# Sounder_Buzzer.net
KiCad netlist of a schematic drawn in Altium Designer
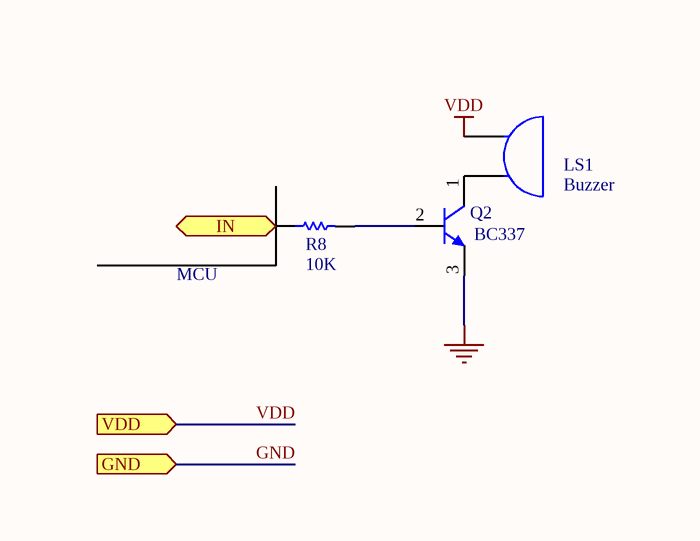
[diagram p0: Sounder_Buzzer.SchDoc]

(export (version "E")
  (design (tool "Eeschema 10.0.6"))
  (components
    (comp (ref "LS1")
      (value "Buzzer")
      (footprint "BUZZER")
      (fields (field (name "MANUFACTURER") "Generic Components") (field (name "PUBLISHER") "Altium Limited"))
      (libsource (lib "Miscellaneous Devices") (part "Buzzer"))
    )
    (comp (ref "Q2")
      (value "BC337")
      (footprint "TO92C")
      (description "NPN Bipolar Transistor")
      (fields
        (field (name "MANUFACTURER") "Generic Components")
        (field (name "Comment") "NPN")
        (field (name "PUBLISHER") "Altium Limited")
      )
      (libsource (lib "Miscellaneous Devices") (part "NPN"))
    )
    (comp (ref "R8")
      (value "10K")
      (footprint "AXIAL-0.4")
      (description "Resistor")
      (fields
        (field (name "MANUFACTURER") "Generic Components")
        (field (name "Comment") "Res1")
        (field (name "PUBLISHER") "Altium Limited")
      )
      (libsource (lib "Miscellaneous Devices") (part "Res1"))
    )
  )
  (nets
    (net (code "1") (name "/IN") (class "Default")
      (node (ref "R8") (pin "1") (pinfunction "1_1") (pintype "passive"))
    )
    (net (code "2") (name "GND") (class "Default")
      (node (ref "Q2") (pin "3") (pinfunction "E_3") (pintype "passive"))
    )
    (net (code "3") (name "Net-(LS1-B)") (class "Default")
      (node (ref "LS1") (pin "2") (pinfunction "B_2") (pintype "passive"))
      (node (ref "Q2") (pin "1") (pinfunction "C_1") (pintype "passive"))
    )
    (net (code "4") (name "Net-(Q2-B)") (class "Default")
      (node (ref "Q2") (pin "2") (pinfunction "B_2") (pintype "passive"))
      (node (ref "R8") (pin "2") (pinfunction "2_2") (pintype "passive"))
    )
    (net (code "5") (name "VDD") (class "Default")
      (node (ref "LS1") (pin "1") (pinfunction "A_1") (pintype "passive"))
    )
  )
)
